# smartcar_shield_cutouts.net
KiCad netlist of a schematic drawn in EAGLE
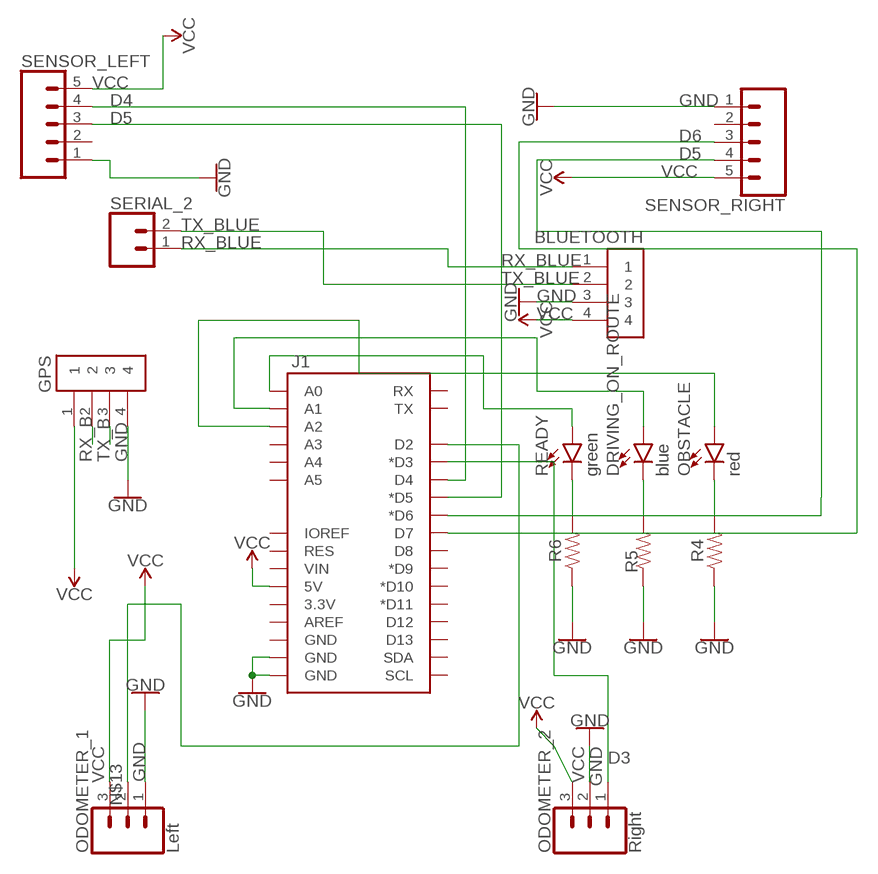
[diagram p0: schematic, sheet 1]

(export (version "E")
  (design (tool "Eeschema 10.0.6"))
  (components
    (comp (ref "BLUETOOTH")
      (value "1X4-BIG")
      (footprint "eagle-import:1X04-BIG")
      (libsource (lib "eagle-import") (part "1X4-BIG"))
    )
    (comp (ref "DRIVING_ON_ROUTE")
      (value "blue")
      (footprint "eagle-import:LED_5MM")
      (libsource (lib "eagle-import") (part "LED5MM"))
    )
    (comp (ref "GPS")
      (value "1X4-BIG")
      (footprint "eagle-import:1X04-BIG")
      (libsource (lib "eagle-import") (part "1X4-BIG"))
    )
    (comp (ref "J1")
      (value "ARDUINO_R3_SHIELDUNO_R3_SHIELD_LOCK")
      (footprint "eagle-import:UNO_R3_SHIELD_LOCK")
      (libsource (lib "eagle-import") (part "ARDUINO_R3_SHIELDUNO_R3_SHIELD_LOCK"))
    )
    (comp (ref "OBSTACLE")
      (value "red")
      (footprint "eagle-import:LED_5MM")
      (libsource (lib "eagle-import") (part "LED5MM"))
    )
    (comp (ref "ODOMETER_1")
      (value "Left")
      (footprint "eagle-import:1X03")
      (libsource (lib "eagle-import") (part "CONN_03"))
    )
    (comp (ref "ODOMETER_2")
      (value "Right")
      (footprint "eagle-import:1X03")
      (libsource (lib "eagle-import") (part "CONN_03"))
    )
    (comp (ref "R4")
      (value "RESISTORAXIAL-0.3")
      (footprint "eagle-import:AXIAL-0.3")
      (libsource (lib "eagle-import") (part "RESISTORAXIAL-0.3"))
    )
    (comp (ref "R5")
      (value "RESISTORAXIAL-0.3")
      (footprint "eagle-import:AXIAL-0.3")
      (libsource (lib "eagle-import") (part "RESISTORAXIAL-0.3"))
    )
    (comp (ref "R6")
      (value "RESISTORAXIAL-0.3")
      (footprint "eagle-import:AXIAL-0.3")
      (libsource (lib "eagle-import") (part "RESISTORAXIAL-0.3"))
    )
    (comp (ref "READY")
      (value "green")
      (footprint "eagle-import:LED_5MM")
      (libsource (lib "eagle-import") (part "LED5MM"))
    )
    (comp (ref "SENSOR_LEFT")
      (value "CONN_05")
      (footprint "eagle-import:1X05")
      (libsource (lib "eagle-import") (part "CONN_05"))
    )
    (comp (ref "SENSOR_RIGHT")
      (value "CONN_05")
      (footprint "eagle-import:1X05")
      (libsource (lib "eagle-import") (part "CONN_05"))
    )
    (comp (ref "SERIAL_2")
      (value "CONN_02")
      (footprint "eagle-import:1X02")
      (libsource (lib "eagle-import") (part "CONN_02"))
    )
  )
  (nets
    (net (code "1") (name "/D3") (class "Default")
      (node (ref "J1") (pin "D3") (pinfunction "*D3_D3") (pintype "bidirectional"))
      (node (ref "ODOMETER_2") (pin "1") (pinfunction "1_1") (pintype "passive"))
    )
    (net (code "2") (name "/D4") (class "Default")
      (node (ref "J1") (pin "D4") (pinfunction "D4_D4") (pintype "bidirectional"))
      (node (ref "SENSOR_LEFT") (pin "4") (pinfunction "4_4") (pintype "passive"))
    )
    (net (code "3") (name "/D5") (class "Default")
      (node (ref "J1") (pin "D5") (pinfunction "*D5_D5") (pintype "bidirectional"))
      (node (ref "J1") (pin "D6") (pinfunction "*D6_D6") (pintype "bidirectional"))
      (node (ref "SENSOR_LEFT") (pin "3") (pinfunction "3_3") (pintype "passive"))
      (node (ref "SENSOR_RIGHT") (pin "4") (pinfunction "4_4") (pintype "passive"))
    )
    (net (code "4") (name "/D6") (class "Default")
      (node (ref "J1") (pin "D7") (pinfunction "D7_D7") (pintype "bidirectional"))
      (node (ref "SENSOR_RIGHT") (pin "3") (pinfunction "3_3") (pintype "passive"))
    )
    (net (code "5") (name "/N$13") (class "Default")
      (node (ref "J1") (pin "D2") (pinfunction "D2_D2") (pintype "bidirectional"))
      (node (ref "ODOMETER_1") (pin "2") (pinfunction "2_2") (pintype "passive"))
    )
    (net (code "6") (name "/RX_B") (class "Default")
      (node (ref "GPS") (pin "2") (pinfunction "2_2") (pintype "bidirectional"))
    )
    (net (code "7") (name "/RX_BLUE") (class "Default")
      (node (ref "BLUETOOTH") (pin "1") (pinfunction "1_1") (pintype "bidirectional"))
      (node (ref "SERIAL_2") (pin "1") (pinfunction "1_1") (pintype "passive"))
    )
    (net (code "8") (name "/TX_B") (class "Default")
      (node (ref "GPS") (pin "3") (pinfunction "3_3") (pintype "bidirectional"))
    )
    (net (code "9") (name "/TX_BLUE") (class "Default")
      (node (ref "BLUETOOTH") (pin "2") (pinfunction "2_2") (pintype "bidirectional"))
      (node (ref "SERIAL_2") (pin "2") (pinfunction "2_2") (pintype "passive"))
    )
    (net (code "10") (name "GND") (class "Default")
      (node (ref "BLUETOOTH") (pin "3") (pinfunction "3_3") (pintype "bidirectional"))
      (node (ref "GPS") (pin "4") (pinfunction "4_4") (pintype "bidirectional"))
      (node (ref "J1") (pin "GND@0") (pinfunction "GND_GND@0") (pintype "bidirectional"))
      (node (ref "J1") (pin "GND@1") (pinfunction "GND_GND@1") (pintype "bidirectional"))
      (node (ref "ODOMETER_1") (pin "1") (pinfunction "1_1") (pintype "passive"))
      (node (ref "ODOMETER_2") (pin "2") (pinfunction "2_2") (pintype "passive"))
      (node (ref "R4") (pin "P$1") (pinfunction "1_P$1") (pintype "passive"))
      (node (ref "R5") (pin "P$1") (pinfunction "1_P$1") (pintype "passive"))
      (node (ref "R6") (pin "P$1") (pinfunction "1_P$1") (pintype "passive"))
      (node (ref "SENSOR_LEFT") (pin "1") (pinfunction "1_1") (pintype "passive"))
      (node (ref "SENSOR_RIGHT") (pin "1") (pinfunction "1_1") (pintype "passive"))
    )
    (net (code "11") (name "Net-(DRIVING_ON_ROUTE-C)") (class "Default")
      (node (ref "DRIVING_ON_ROUTE") (pin "K") (pinfunction "C_K") (pintype "passive"))
      (node (ref "R5") (pin "P$2") (pinfunction "2_P$2") (pintype "passive"))
    )
    (net (code "12") (name "Net-(DRIVING_ON_ROUTE-PadA)") (class "Default")
      (node (ref "DRIVING_ON_ROUTE") (pin "A") (pinfunction "A_A") (pintype "passive"))
      (node (ref "J1") (pin "A1") (pinfunction "A1_A1") (pintype "bidirectional"))
    )
    (net (code "13") (name "Net-(J1-PadA0)") (class "Default")
      (node (ref "J1") (pin "A0") (pinfunction "A0_A0") (pintype "bidirectional"))
      (node (ref "READY") (pin "A") (pinfunction "A_A") (pintype "passive"))
    )
    (net (code "14") (name "Net-(J1-PadA2)") (class "Default")
      (node (ref "J1") (pin "A2") (pinfunction "A2_A2") (pintype "bidirectional"))
      (node (ref "OBSTACLE") (pin "A") (pinfunction "A_A") (pintype "passive"))
    )
    (net (code "15") (name "Net-(OBSTACLE-C)") (class "Default")
      (node (ref "OBSTACLE") (pin "K") (pinfunction "C_K") (pintype "passive"))
      (node (ref "R4") (pin "P$2") (pinfunction "2_P$2") (pintype "passive"))
    )
    (net (code "16") (name "Net-(R6-2)") (class "Default")
      (node (ref "R6") (pin "P$2") (pinfunction "2_P$2") (pintype "passive"))
      (node (ref "READY") (pin "K") (pinfunction "C_K") (pintype "passive"))
    )
    (net (code "17") (name "VCC") (class "Default")
      (node (ref "BLUETOOTH") (pin "4") (pinfunction "4_4") (pintype "bidirectional"))
      (node (ref "GPS") (pin "1") (pinfunction "1_1") (pintype "bidirectional"))
      (node (ref "J1") (pin "5V") (pinfunction "5V_5V") (pintype "bidirectional"))
      (node (ref "ODOMETER_1") (pin "3") (pinfunction "3_3") (pintype "passive"))
      (node (ref "ODOMETER_2") (pin "3") (pinfunction "3_3") (pintype "passive"))
      (node (ref "SENSOR_LEFT") (pin "5") (pinfunction "5_5") (pintype "passive"))
      (node (ref "SENSOR_RIGHT") (pin "5") (pinfunction "5_5") (pintype "passive"))
    )
    (net (code "18") (name "unconnected-(J1-*D9-PadD9)") (class "Default")
      (node (ref "J1") (pin "D9") (pinfunction "*D9_D9") (pintype "bidirectional"))
    )
    (net (code "19") (name "unconnected-(J1-*D10-PadD10)") (class "Default")
      (node (ref "J1") (pin "D10") (pinfunction "*D10_D10") (pintype "bidirectional"))
    )
    (net (code "20") (name "unconnected-(J1-*D11-PadD11)") (class "Default")
      (node (ref "J1") (pin "D11") (pinfunction "*D11_D11") (pintype "bidirectional"))
    )
    (net (code "21") (name "unconnected-(J1-GND-PadGND@2)") (class "Default")
      (node (ref "J1") (pin "GND@2") (pinfunction "GND_GND@2") (pintype "bidirectional"))
    )
    (net (code "22") (name "unconnected-(J1-Pad3.3V)") (class "Default")
      (node (ref "J1") (pin "3.3V") (pinfunction "3.3V_3.3V") (pintype "bidirectional"))
    )
    (net (code "23") (name "unconnected-(J1-PadA3)") (class "Default")
      (node (ref "J1") (pin "A3") (pinfunction "A3_A3") (pintype "bidirectional"))
    )
    (net (code "24") (name "unconnected-(J1-PadA4)") (class "Default")
      (node (ref "J1") (pin "A4") (pinfunction "A4_A4") (pintype "bidirectional"))
    )
    (net (code "25") (name "unconnected-(J1-PadA5)") (class "Default")
      (node (ref "J1") (pin "A5") (pinfunction "A5_A5") (pintype "bidirectional"))
    )
    (net (code "26") (name "unconnected-(J1-PadAREF)") (class "Default")
      (node (ref "J1") (pin "AREF") (pinfunction "AREF_AREF") (pintype "bidirectional"))
    )
    (net (code "27") (name "unconnected-(J1-PadD8)") (class "Default")
      (node (ref "J1") (pin "D8") (pinfunction "D8_D8") (pintype "bidirectional"))
    )
    (net (code "28") (name "unconnected-(J1-PadD12)") (class "Default")
      (node (ref "J1") (pin "D12") (pinfunction "D12_D12") (pintype "bidirectional"))
    )
    (net (code "29") (name "unconnected-(J1-PadD13)") (class "Default")
      (node (ref "J1") (pin "D13") (pinfunction "D13_D13") (pintype "bidirectional"))
    )
    (net (code "30") (name "unconnected-(J1-PadIOREF)") (class "Default")
      (node (ref "J1") (pin "IOREF") (pinfunction "IOREF_IOREF") (pintype "bidirectional"))
    )
    (net (code "31") (name "unconnected-(J1-PadRES)") (class "Default")
      (node (ref "J1") (pin "RES") (pinfunction "RES_RES") (pintype "bidirectional"))
    )
    (net (code "32") (name "unconnected-(J1-PadRX)") (class "Default")
      (node (ref "J1") (pin "RX") (pinfunction "RX_RX") (pintype "bidirectional"))
    )
    (net (code "33") (name "unconnected-(J1-PadSCL)") (class "Default")
      (node (ref "J1") (pin "SCL") (pinfunction "SCL_SCL") (pintype "bidirectional"))
    )
    (net (code "34") (name "unconnected-(J1-PadSDA)") (class "Default")
      (node (ref "J1") (pin "SDA") (pinfunction "SDA_SDA") (pintype "bidirectional"))
    )
    (net (code "35") (name "unconnected-(J1-PadTX)") (class "Default")
      (node (ref "J1") (pin "TX") (pinfunction "TX_TX") (pintype "bidirectional"))
    )
    (net (code "36") (name "unconnected-(J1-PadVIN)") (class "Default")
      (node (ref "J1") (pin "VIN") (pinfunction "VIN_VIN") (pintype "bidirectional"))
    )
    (net (code "37") (name "unconnected-(SENSOR_LEFT-Pad2)") (class "Default")
      (node (ref "SENSOR_LEFT") (pin "2") (pinfunction "2_2") (pintype "passive"))
    )
    (net (code "38") (name "unconnected-(SENSOR_RIGHT-Pad2)") (class "Default")
      (node (ref "SENSOR_RIGHT") (pin "2") (pinfunction "2_2") (pintype "passive"))
    )
  )
)
